# cut_off.net
KiCad netlist of a schematic drawn in EAGLE
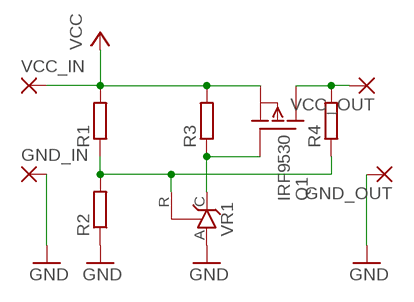
[diagram p0: schematic, sheet 1]

(export (version "E")
  (design (tool "Eeschema 10.0.6"))
  (components
    (comp (ref "GND_IN")
      (value "2,15/1,0")
      (footprint "eagle-import:2,15_1,0")
      (libsource (lib "eagle-import") (part "2,15/1,0"))
    )
    (comp (ref "GND_OUT")
      (value "2,15/1,0")
      (footprint "eagle-import:2,15_1,0")
      (libsource (lib "eagle-import") (part "2,15/1,0"))
    )
    (comp (ref "Q1")
      (value "IRF9530")
      (footprint "eagle-import:TO220")
      (libsource (lib "eagle-import") (part "IRF9530"))
    )
    (comp (ref "R1")
      (value "R-EU_R0805")
      (footprint "eagle-import:R0805")
      (libsource (lib "eagle-import") (part "R-EU_R0805"))
    )
    (comp (ref "R2")
      (value "R-EU_R0805")
      (footprint "eagle-import:R0805")
      (libsource (lib "eagle-import") (part "R-EU_R0805"))
    )
    (comp (ref "R3")
      (value "R-EU_R0805")
      (footprint "eagle-import:R0805")
      (libsource (lib "eagle-import") (part "R-EU_R0805"))
    )
    (comp (ref "R4")
      (value "R-EU_R0805")
      (footprint "eagle-import:R0805")
      (libsource (lib "eagle-import") (part "R-EU_R0805"))
    )
    (comp (ref "VCC_IN")
      (value "2,15/1,0")
      (footprint "eagle-import:2,15_1,0")
      (libsource (lib "eagle-import") (part "2,15/1,0"))
    )
    (comp (ref "VCC_OUT")
      (value "2,15/1,0")
      (footprint "eagle-import:2,15_1,0")
      (libsource (lib "eagle-import") (part "2,15/1,0"))
    )
    (comp (ref "VR1")
      (value "TL431CLP")
      (footprint "eagle-import:TO92-CLP")
      (libsource (lib "eagle-import") (part "TL431CLP"))
    )
  )
  (nets
    (net (code "1") (name "GND") (class "Default")
      (node (ref "GND_IN") (pin "1") (pinfunction "P_1") (pintype "passive"))
      (node (ref "GND_OUT") (pin "1") (pinfunction "P_1") (pintype "passive"))
      (node (ref "R2") (pin "1") (pinfunction "1_1") (pintype "passive"))
      (node (ref "VR1") (pin "A") (pinfunction "A_A") (pintype "passive"))
    )
    (net (code "2") (name "Net-(Q1-D)") (class "Default")
      (node (ref "Q1") (pin "2") (pinfunction "D_2") (pintype "passive"))
      (node (ref "R4") (pin "2") (pinfunction "2_2") (pintype "passive"))
      (node (ref "VCC_OUT") (pin "1") (pinfunction "P_1") (pintype "passive"))
    )
    (net (code "3") (name "Net-(Q1-G)") (class "Default")
      (node (ref "Q1") (pin "1") (pinfunction "G_1") (pintype "passive"))
      (node (ref "R3") (pin "1") (pinfunction "1_1") (pintype "passive"))
      (node (ref "VR1") (pin "C") (pinfunction "C_C") (pintype "passive"))
    )
    (net (code "4") (name "Net-(R1-Pad1)") (class "Default")
      (node (ref "R1") (pin "1") (pinfunction "1_1") (pintype "passive"))
      (node (ref "R2") (pin "2") (pinfunction "2_2") (pintype "passive"))
      (node (ref "R4") (pin "1") (pinfunction "1_1") (pintype "passive"))
      (node (ref "VR1") (pin "R") (pinfunction "R_R") (pintype "passive"))
    )
    (net (code "5") (name "VCC") (class "Default")
      (node (ref "Q1") (pin "3") (pinfunction "S_3") (pintype "passive"))
      (node (ref "R1") (pin "2") (pinfunction "2_2") (pintype "passive"))
      (node (ref "R3") (pin "2") (pinfunction "2_2") (pintype "passive"))
      (node (ref "VCC_IN") (pin "1") (pinfunction "P_1") (pintype "passive"))
    )
  )
)
